# top-100-68-shield.net
KiCad netlist of a schematic drawn in EAGLE
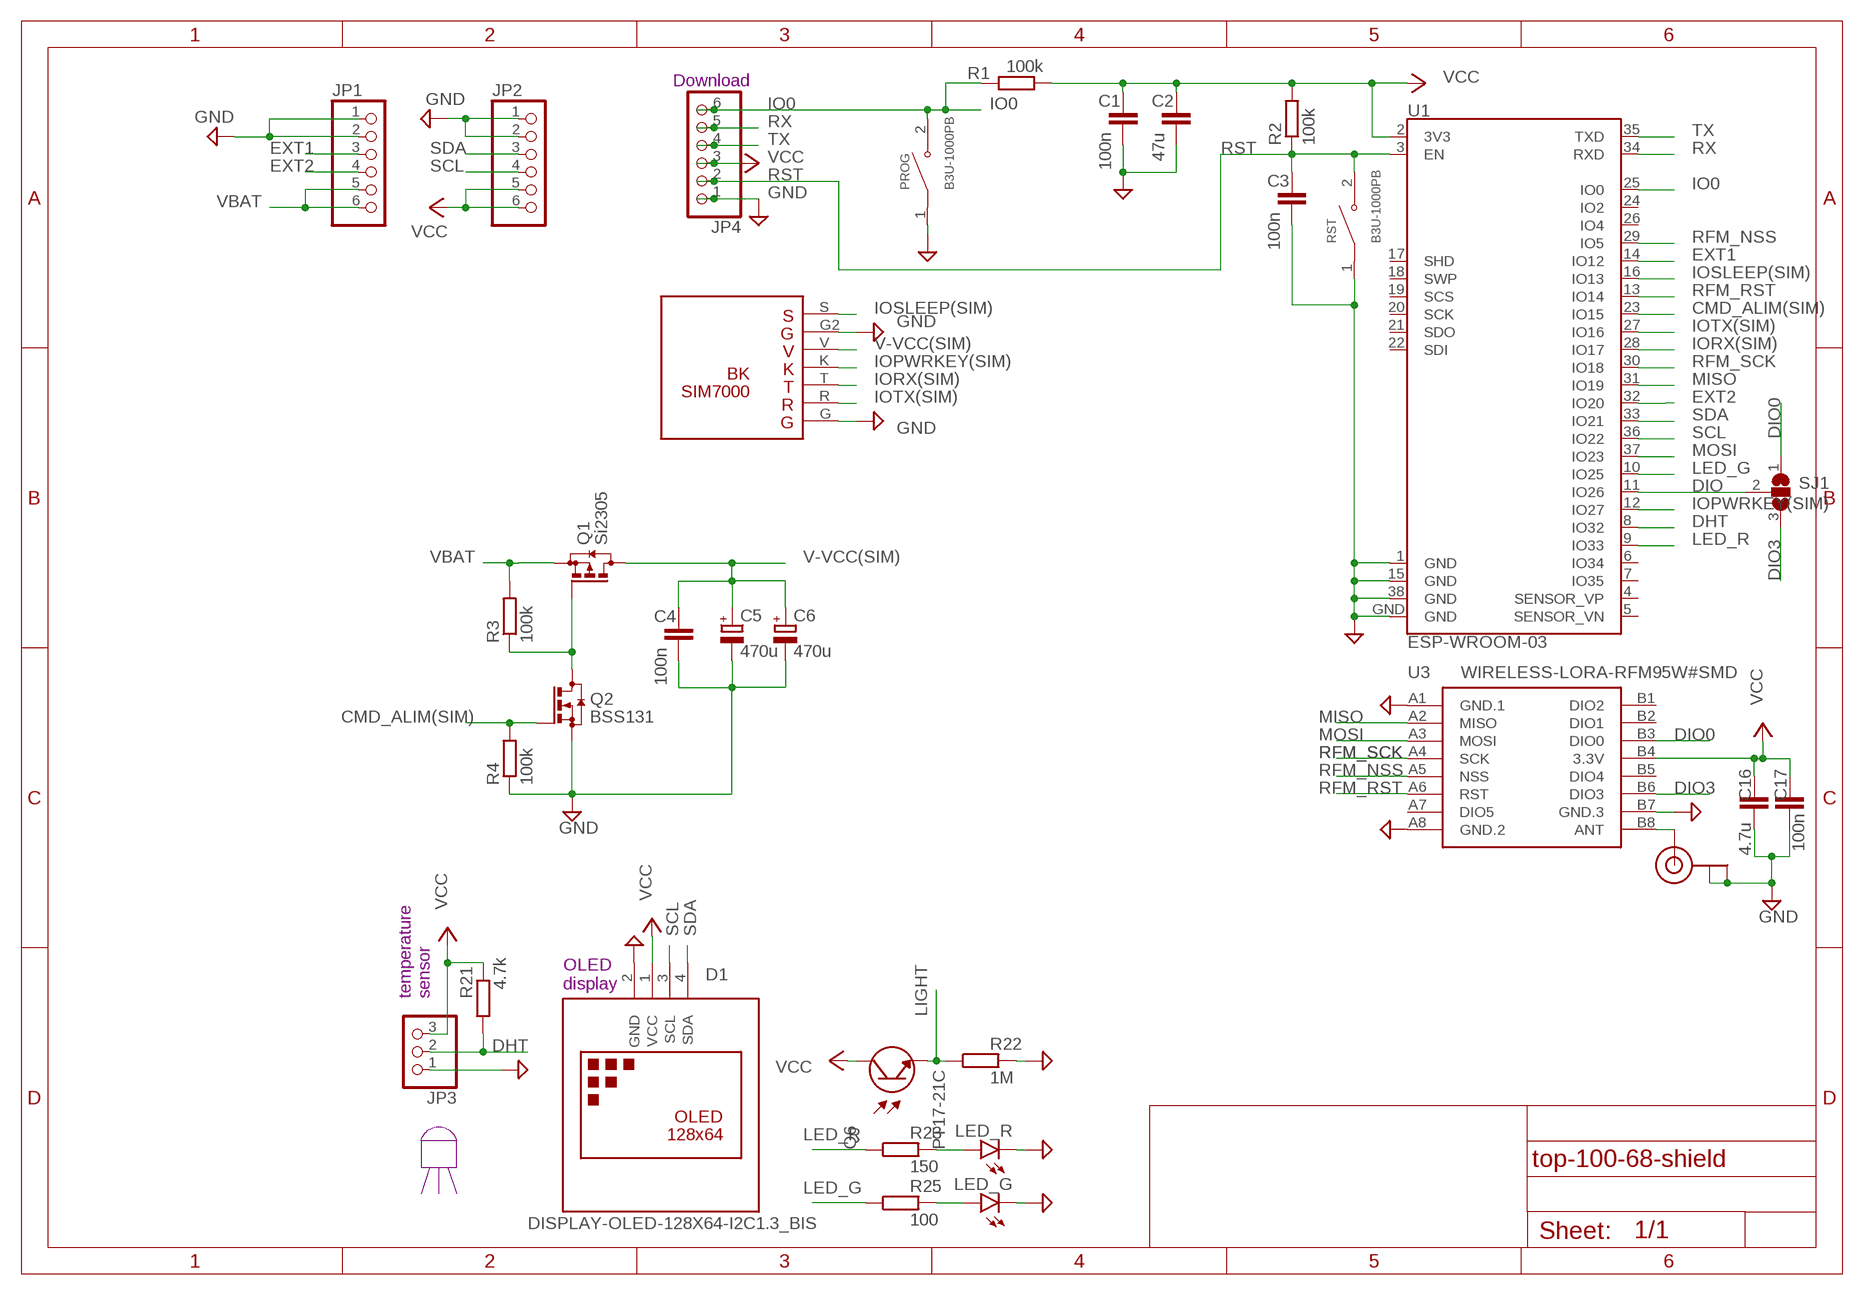
[diagram p0: schematic, sheet 1]

(export (version "E")
  (design (tool "Eeschema 10.0.6"))
  (components
    (comp (ref "C1")
      (value "100n")
      (footprint "eagle-import:C1206")
      (libsource (lib "eagle-import") (part "CC1206"))
    )
    (comp (ref "C2")
      (value "47u")
      (footprint "eagle-import:C0805")
      (libsource (lib "eagle-import") (part "C"))
    )
    (comp (ref "C3")
      (value "100n")
      (footprint "eagle-import:C1206")
      (libsource (lib "eagle-import") (part "CC1206"))
    )
    (comp (ref "C4")
      (value "100n")
      (footprint "eagle-import:C1206")
      (libsource (lib "eagle-import") (part "CC1206"))
    )
    (comp (ref "C5")
      (value "470u")
      (footprint "eagle-import:CT7343")
      (libsource (lib "eagle-import") (part "CPOL-EUCT7343"))
    )
    (comp (ref "C6")
      (value "470u")
      (footprint "eagle-import:CT7343")
      (libsource (lib "eagle-import") (part "CPOL-EUCT7343"))
    )
    (comp (ref "C16")
      (value "4.7u")
      (footprint "eagle-import:C1210")
      (libsource (lib "eagle-import") (part "CC1210"))
    )
    (comp (ref "C17")
      (value "100n")
      (footprint "eagle-import:C1206")
      (libsource (lib "eagle-import") (part "CC1206"))
    )
    (comp (ref "D1")
      (value "DISPLAY-OLED-128X64-I2C1.3_BIS")
      (footprint "eagle-import:DISPLAY-OLED-128X64-1.3-I2C_BIS")
      (libsource (lib "eagle-import") (part "DISPLAY-OLED-128X64-I2C1.3_BIS"))
    )
    (comp (ref "J1")
      (value "U.FL")
      (footprint "eagle-import:U.FL")
      (libsource (lib "eagle-import") (part "U.FL"))
    )
    (comp (ref "JP1")
      (value "PINHD-1X6S")
      (footprint "eagle-import:1X06S")
      (libsource (lib "eagle-import") (part "PINHD-1X6S"))
    )
    (comp (ref "JP2")
      (value "PINHD-1X6S")
      (footprint "eagle-import:1X06S")
      (libsource (lib "eagle-import") (part "PINHD-1X6S"))
    )
    (comp (ref "JP3")
      (value "PINHD-1X3")
      (footprint "eagle-import:1X03")
      (libsource (lib "eagle-import") (part "PINHD-1X3"))
    )
    (comp (ref "JP4")
      (value "PINHD-1X6S")
      (footprint "eagle-import:1X06S")
      (libsource (lib "eagle-import") (part "PINHD-1X6S"))
    )
    (comp (ref "LED_G")
      (value "LEDSMT1206")
      (footprint "eagle-import:1206")
      (libsource (lib "eagle-import") (part "LEDSMT1206"))
    )
    (comp (ref "LED_R")
      (value "LEDSMT1206")
      (footprint "eagle-import:1206")
      (libsource (lib "eagle-import") (part "LEDSMT1206"))
    )
    (comp (ref "PROG")
      (value "B3U-1000PB")
      (footprint "eagle-import:SW_B3U-1000PB")
      (libsource (lib "eagle-import") (part "B3U-1000PB"))
    )
    (comp (ref "Q1")
      (value "Si2305")
      (footprint "eagle-import:SOT23")
      (libsource (lib "eagle-import") (part "BSS84"))
    )
    (comp (ref "Q2")
      (value "BSS131")
      (footprint "eagle-import:SOT23")
      (libsource (lib "eagle-import") (part "BSS123"))
    )
    (comp (ref "Q6")
      (value "PT17-21C")
      (footprint "eagle-import:0805")
      (libsource (lib "eagle-import") (part "PT17-21C"))
    )
    (comp (ref "R1")
      (value "100k")
      (footprint "eagle-import:R1206")
      (libsource (lib "eagle-import") (part "RR1206"))
    )
    (comp (ref "R2")
      (value "100k")
      (footprint "eagle-import:R1206")
      (libsource (lib "eagle-import") (part "RR1206"))
    )
    (comp (ref "R3")
      (value "100k")
      (footprint "eagle-import:R1206")
      (libsource (lib "eagle-import") (part "RR1206"))
    )
    (comp (ref "R4")
      (value "100k")
      (footprint "eagle-import:R1206")
      (libsource (lib "eagle-import") (part "RR1206"))
    )
    (comp (ref "R21")
      (value "4.7k")
      (footprint "eagle-import:R1206")
      (libsource (lib "eagle-import") (part "RR1206"))
    )
    (comp (ref "R22")
      (value "1M")
      (footprint "eagle-import:R1206")
      (libsource (lib "eagle-import") (part "RR1206"))
    )
    (comp (ref "R23")
      (value "150")
      (footprint "eagle-import:R1206")
      (libsource (lib "eagle-import") (part "RR1206"))
    )
    (comp (ref "R25")
      (value "100")
      (footprint "eagle-import:R1206")
      (libsource (lib "eagle-import") (part "RR1206"))
    )
    (comp (ref "RST")
      (value "B3U-1000PB")
      (footprint "eagle-import:SW_B3U-1000PB")
      (libsource (lib "eagle-import") (part "B3U-1000PB"))
    )
    (comp (ref "SJ1")
      (value "SJ2W")
      (footprint "eagle-import:SJ_2")
      (libsource (lib "eagle-import") (part "SJ2W"))
    )
    (comp (ref "U1")
      (value "ESP-WROOM-03")
      (footprint "eagle-import:ESP-WROOM-03")
      (libsource (lib "eagle-import") (part "ESP-WROOM-03"))
    )
    (comp (ref "U2")
      (value "BK7000-V2")
      (footprint "eagle-import:SIM7000-BK")
      (libsource (lib "eagle-import") (part "BK7000-V2"))
    )
    (comp (ref "U3")
      (value "WIRELESS-LORA-RFM95W#SMD")
      (footprint "eagle-import:WIRELESS-LORA-RFM95W#SMD")
      (libsource (lib "eagle-import") (part "WIRELESS-LORA-RFM95W#SMD"))
    )
  )
  (nets
    (net (code "1") (name "/CMD_ALIM(SIM)") (class "Default")
      (node (ref "Q2") (pin "1") (pinfunction "G_1") (pintype "passive"))
      (node (ref "R4") (pin "2") (pinfunction "2_2") (pintype "passive"))
      (node (ref "U1") (pin "23") (pinfunction "IO15_23") (pintype "bidirectional"))
    )
    (net (code "2") (name "/DHT") (class "Default")
      (node (ref "JP3") (pin "2") (pinfunction "2_2") (pintype "passive"))
      (node (ref "R21") (pin "1") (pinfunction "1_1") (pintype "passive"))
      (node (ref "U1") (pin "8") (pinfunction "IO32_8") (pintype "bidirectional"))
    )
    (net (code "3") (name "/DIO") (class "Default")
      (node (ref "SJ1") (pin "2") (pinfunction "2_2") (pintype "passive"))
      (node (ref "U1") (pin "11") (pinfunction "IO26_11") (pintype "bidirectional"))
    )
    (net (code "4") (name "/DIO0") (class "Default")
      (node (ref "SJ1") (pin "1") (pinfunction "1_1") (pintype "passive"))
      (node (ref "U3") (pin "B3") (pinfunction "DIO0_B3") (pintype "bidirectional"))
    )
    (net (code "5") (name "/DIO3") (class "Default")
      (node (ref "SJ1") (pin "3") (pinfunction "3_3") (pintype "passive"))
      (node (ref "U3") (pin "B6") (pinfunction "DIO3_B6") (pintype "bidirectional"))
    )
    (net (code "6") (name "/EXT1") (class "Default")
      (node (ref "JP1") (pin "3") (pinfunction "3_3") (pintype "passive"))
      (node (ref "U1") (pin "14") (pinfunction "IO12_14") (pintype "bidirectional"))
    )
    (net (code "7") (name "/EXT2") (class "Default")
      (node (ref "JP1") (pin "4") (pinfunction "4_4") (pintype "passive"))
      (node (ref "U1") (pin "32") (pinfunction "IO20_32") (pintype "bidirectional"))
    )
    (net (code "8") (name "/IO0") (class "Default")
      (node (ref "JP4") (pin "6") (pinfunction "6_6") (pintype "passive"))
      (node (ref "PROG") (pin "2") (pinfunction "2_2") (pintype "passive"))
      (node (ref "R1") (pin "2") (pinfunction "2_2") (pintype "passive"))
      (node (ref "U1") (pin "25") (pinfunction "IO0_25") (pintype "bidirectional"))
    )
    (net (code "9") (name "/IOPWRKEY(SIM)") (class "Default")
      (node (ref "U1") (pin "12") (pinfunction "IO27_12") (pintype "bidirectional"))
      (node (ref "U2") (pin "K") (pinfunction "K_K") (pintype "output"))
    )
    (net (code "10") (name "/IORX(SIM)") (class "Default")
      (node (ref "U1") (pin "28") (pinfunction "IO17_28") (pintype "bidirectional"))
      (node (ref "U2") (pin "T") (pinfunction "T_T") (pintype "output"))
    )
    (net (code "11") (name "/IOSLEEP(SIM)") (class "Default")
      (node (ref "U1") (pin "16") (pinfunction "IO13_16") (pintype "bidirectional"))
      (node (ref "U2") (pin "S") (pinfunction "S_S") (pintype "input"))
    )
    (net (code "12") (name "/IOTX(SIM)") (class "Default")
      (node (ref "U1") (pin "27") (pinfunction "IO16_27") (pintype "bidirectional"))
      (node (ref "U2") (pin "R") (pinfunction "R_R") (pintype "input"))
    )
    (net (code "13") (name "/LED_G") (class "Default")
      (node (ref "R25") (pin "1") (pinfunction "1_1") (pintype "passive"))
      (node (ref "U1") (pin "10") (pinfunction "IO25_10") (pintype "bidirectional"))
    )
    (net (code "14") (name "/LED_R") (class "Default")
      (node (ref "R23") (pin "1") (pinfunction "1_1") (pintype "passive"))
      (node (ref "U1") (pin "9") (pinfunction "IO33_9") (pintype "bidirectional"))
    )
    (net (code "15") (name "/LIGHT") (class "Default")
      (node (ref "Q6") (pin "1") (pinfunction "E_1") (pintype "passive"))
      (node (ref "R22") (pin "1") (pinfunction "1_1") (pintype "passive"))
    )
    (net (code "16") (name "/MISO") (class "Default")
      (node (ref "U1") (pin "31") (pinfunction "IO19_31") (pintype "bidirectional"))
      (node (ref "U3") (pin "A2") (pinfunction "MISO_A2") (pintype "bidirectional"))
    )
    (net (code "17") (name "/MOSI") (class "Default")
      (node (ref "U1") (pin "37") (pinfunction "IO23_37") (pintype "bidirectional"))
      (node (ref "U3") (pin "A3") (pinfunction "MOSI_A3") (pintype "bidirectional"))
    )
    (net (code "18") (name "/RFM_NSS") (class "Default")
      (node (ref "U1") (pin "29") (pinfunction "IO5_29") (pintype "bidirectional"))
      (node (ref "U3") (pin "A5") (pinfunction "NSS_A5") (pintype "bidirectional"))
    )
    (net (code "19") (name "/RFM_RST") (class "Default")
      (node (ref "U1") (pin "13") (pinfunction "IO14_13") (pintype "bidirectional"))
      (node (ref "U3") (pin "A6") (pinfunction "RST_A6") (pintype "bidirectional"))
    )
    (net (code "20") (name "/RFM_SCK") (class "Default")
      (node (ref "U1") (pin "30") (pinfunction "IO18_30") (pintype "bidirectional"))
      (node (ref "U3") (pin "A4") (pinfunction "SCK_A4") (pintype "bidirectional"))
    )
    (net (code "21") (name "/RST") (class "Default")
      (node (ref "C3") (pin "1") (pinfunction "1_1") (pintype "passive"))
      (node (ref "JP4") (pin "2") (pinfunction "2_2") (pintype "passive"))
      (node (ref "R2") (pin "1") (pinfunction "1_1") (pintype "passive"))
      (node (ref "RST") (pin "2") (pinfunction "2_2") (pintype "passive"))
      (node (ref "U1") (pin "3") (pinfunction "EN_3") (pintype "bidirectional"))
    )
    (net (code "22") (name "/RX") (class "Default")
      (node (ref "JP4") (pin "5") (pinfunction "5_5") (pintype "passive"))
      (node (ref "U1") (pin "34") (pinfunction "RXD_34") (pintype "bidirectional"))
    )
    (net (code "23") (name "/SCL") (class "Default")
      (node (ref "D1") (pin "3") (pinfunction "SCL_3") (pintype "bidirectional"))
      (node (ref "JP2") (pin "4") (pinfunction "4_4") (pintype "passive"))
      (node (ref "U1") (pin "36") (pinfunction "IO22_36") (pintype "bidirectional"))
    )
    (net (code "24") (name "/SDA") (class "Default")
      (node (ref "D1") (pin "4") (pinfunction "SDA_4") (pintype "bidirectional"))
      (node (ref "JP2") (pin "3") (pinfunction "3_3") (pintype "passive"))
      (node (ref "U1") (pin "33") (pinfunction "IO21_33") (pintype "bidirectional"))
    )
    (net (code "25") (name "/TX") (class "Default")
      (node (ref "JP4") (pin "4") (pinfunction "4_4") (pintype "passive"))
      (node (ref "U1") (pin "35") (pinfunction "TXD_35") (pintype "bidirectional"))
    )
    (net (code "26") (name "/V-VCC(SIM)") (class "Default")
      (node (ref "C4") (pin "1") (pinfunction "1_1") (pintype "passive"))
      (node (ref "C5") (pin "+") (pinfunction "+_+") (pintype "passive"))
      (node (ref "C6") (pin "+") (pinfunction "+_+") (pintype "passive"))
      (node (ref "Q1") (pin "3") (pinfunction "D_3") (pintype "passive"))
      (node (ref "U2") (pin "V") (pinfunction "V_V") (pintype "power_in"))
    )
    (net (code "27") (name "/VBAT") (class "Default")
      (node (ref "JP1") (pin "5") (pinfunction "5_5") (pintype "passive"))
      (node (ref "JP1") (pin "6") (pinfunction "6_6") (pintype "passive"))
      (node (ref "Q1") (pin "2") (pinfunction "S_2") (pintype "passive"))
      (node (ref "R3") (pin "2") (pinfunction "2_2") (pintype "passive"))
    )
    (net (code "28") (name "GND") (class "Default")
      (node (ref "C1") (pin "2") (pinfunction "2_2") (pintype "passive"))
      (node (ref "C16") (pin "2") (pinfunction "2_2") (pintype "passive"))
      (node (ref "C17") (pin "2") (pinfunction "2_2") (pintype "passive"))
      (node (ref "C2") (pin "2") (pinfunction "2_2") (pintype "passive"))
      (node (ref "C3") (pin "2") (pinfunction "2_2") (pintype "passive"))
      (node (ref "C4") (pin "2") (pinfunction "2_2") (pintype "passive"))
      (node (ref "C5") (pin "-") (pinfunction "-_-") (pintype "passive"))
      (node (ref "C6") (pin "-") (pinfunction "-_-") (pintype "passive"))
      (node (ref "D1") (pin "2") (pinfunction "GND_2") (pintype "power_in"))
      (node (ref "J1") (pin "1") (pinfunction "GND_1") (pintype "passive"))
      (node (ref "J1") (pin "2") (pinfunction "GND_2") (pintype "passive"))
      (node (ref "JP1") (pin "1") (pinfunction "1_1") (pintype "passive"))
      (node (ref "JP1") (pin "2") (pinfunction "2_2") (pintype "passive"))
      (node (ref "JP2") (pin "1") (pinfunction "1_1") (pintype "passive"))
      (node (ref "JP2") (pin "2") (pinfunction "2_2") (pintype "passive"))
      (node (ref "JP3") (pin "1") (pinfunction "1_1") (pintype "passive"))
      (node (ref "JP4") (pin "1") (pinfunction "1_1") (pintype "passive"))
      (node (ref "LED_G") (pin "C") (pinfunction "C_C") (pintype "passive"))
      (node (ref "LED_R") (pin "C") (pinfunction "C_C") (pintype "passive"))
      (node (ref "PROG") (pin "1") (pinfunction "1_1") (pintype "passive"))
      (node (ref "Q2") (pin "2") (pinfunction "S_2") (pintype "passive"))
      (node (ref "R22") (pin "2") (pinfunction "2_2") (pintype "passive"))
      (node (ref "R4") (pin "1") (pinfunction "1_1") (pintype "passive"))
      (node (ref "RST") (pin "1") (pinfunction "1_1") (pintype "passive"))
      (node (ref "U1") (pin "1") (pinfunction "GND_1") (pintype "bidirectional"))
      (node (ref "U1") (pin "15") (pinfunction "GND_15") (pintype "bidirectional"))
      (node (ref "U1") (pin "38") (pinfunction "GND_38") (pintype "bidirectional"))
      (node (ref "U1") (pin "GND") (pinfunction "GND_GND") (pintype "bidirectional"))
      (node (ref "U2") (pin "G") (pinfunction "G_G") (pintype "power_in"))
      (node (ref "U2") (pin "G2") (pinfunction "G2_G2") (pintype "power_in"))
      (node (ref "U3") (pin "A1") (pinfunction "GND.1_A1") (pintype "power_in"))
      (node (ref "U3") (pin "A8") (pinfunction "GND.2_A8") (pintype "power_in"))
      (node (ref "U3") (pin "B7") (pinfunction "GND.3_B7") (pintype "power_in"))
    )
    (net (code "29") (name "Net-(J1-SIGNAL)") (class "Default")
      (node (ref "J1") (pin "3") (pinfunction "SIGNAL_3") (pintype "passive"))
      (node (ref "U3") (pin "B8") (pinfunction "ANT_B8") (pintype "passive"))
    )
    (net (code "30") (name "Net-(LED_G-PadA)") (class "Default")
      (node (ref "LED_G") (pin "A") (pinfunction "A_A") (pintype "passive"))
      (node (ref "R25") (pin "2") (pinfunction "2_2") (pintype "passive"))
    )
    (net (code "31") (name "Net-(LED_R-PadA)") (class "Default")
      (node (ref "LED_R") (pin "A") (pinfunction "A_A") (pintype "passive"))
      (node (ref "R23") (pin "2") (pinfunction "2_2") (pintype "passive"))
    )
    (net (code "32") (name "Net-(Q1-G)") (class "Default")
      (node (ref "Q1") (pin "1") (pinfunction "G_1") (pintype "passive"))
      (node (ref "Q2") (pin "3") (pinfunction "D_3") (pintype "passive"))
      (node (ref "R3") (pin "1") (pinfunction "1_1") (pintype "passive"))
    )
    (net (code "33") (name "VCC") (class "Default")
      (node (ref "C1") (pin "1") (pinfunction "1_1") (pintype "passive"))
      (node (ref "C16") (pin "1") (pinfunction "1_1") (pintype "passive"))
      (node (ref "C17") (pin "1") (pinfunction "1_1") (pintype "passive"))
      (node (ref "C2") (pin "1") (pinfunction "1_1") (pintype "passive"))
      (node (ref "D1") (pin "1") (pinfunction "VCC_1") (pintype "power_in"))
      (node (ref "JP2") (pin "5") (pinfunction "5_5") (pintype "passive"))
      (node (ref "JP2") (pin "6") (pinfunction "6_6") (pintype "passive"))
      (node (ref "JP3") (pin "3") (pinfunction "3_3") (pintype "passive"))
      (node (ref "JP4") (pin "3") (pinfunction "3_3") (pintype "passive"))
      (node (ref "Q6") (pin "2") (pinfunction "C_2") (pintype "passive"))
      (node (ref "R1") (pin "1") (pinfunction "1_1") (pintype "passive"))
      (node (ref "R2") (pin "2") (pinfunction "2_2") (pintype "passive"))
      (node (ref "R21") (pin "2") (pinfunction "2_2") (pintype "passive"))
      (node (ref "U1") (pin "2") (pinfunction "3V3_2") (pintype "bidirectional"))
      (node (ref "U3") (pin "B4") (pinfunction "3.3V_B4") (pintype "power_in"))
    )
    (net (code "34") (name "unconnected-(U1-IO2-Pad24)") (class "Default")
      (node (ref "U1") (pin "24") (pinfunction "IO2_24") (pintype "bidirectional"))
    )
    (net (code "35") (name "unconnected-(U1-IO4-Pad26)") (class "Default")
      (node (ref "U1") (pin "26") (pinfunction "IO4_26") (pintype "bidirectional"))
    )
    (net (code "36") (name "unconnected-(U1-IO34-Pad6)") (class "Default")
      (node (ref "U1") (pin "6") (pinfunction "IO34_6") (pintype "bidirectional"))
    )
    (net (code "37") (name "unconnected-(U1-IO35-Pad7)") (class "Default")
      (node (ref "U1") (pin "7") (pinfunction "IO35_7") (pintype "bidirectional"))
    )
    (net (code "38") (name "unconnected-(U1-SCK-Pad20)") (class "Default")
      (node (ref "U1") (pin "20") (pinfunction "SCK_20") (pintype "bidirectional"))
    )
    (net (code "39") (name "unconnected-(U1-SCS-Pad19)") (class "Default")
      (node (ref "U1") (pin "19") (pinfunction "SCS_19") (pintype "bidirectional"))
    )
    (net (code "40") (name "unconnected-(U1-SDI-Pad22)") (class "Default")
      (node (ref "U1") (pin "22") (pinfunction "SDI_22") (pintype "bidirectional"))
    )
    (net (code "41") (name "unconnected-(U1-SDO-Pad21)") (class "Default")
      (node (ref "U1") (pin "21") (pinfunction "SDO_21") (pintype "bidirectional"))
    )
    (net (code "42") (name "unconnected-(U1-SENSOR_VN-Pad5)") (class "Default")
      (node (ref "U1") (pin "5") (pinfunction "SENSOR_VN_5") (pintype "bidirectional"))
    )
    (net (code "43") (name "unconnected-(U1-SENSOR_VP-Pad4)") (class "Default")
      (node (ref "U1") (pin "4") (pinfunction "SENSOR_VP_4") (pintype "bidirectional"))
    )
    (net (code "44") (name "unconnected-(U1-SHD-Pad17)") (class "Default")
      (node (ref "U1") (pin "17") (pinfunction "SHD_17") (pintype "bidirectional"))
    )
    (net (code "45") (name "unconnected-(U1-SWP-Pad18)") (class "Default")
      (node (ref "U1") (pin "18") (pinfunction "SWP_18") (pintype "bidirectional"))
    )
    (net (code "46") (name "unconnected-(U3-DIO1-PadB2)") (class "Default")
      (node (ref "U3") (pin "B2") (pinfunction "DIO1_B2") (pintype "bidirectional"))
    )
    (net (code "47") (name "unconnected-(U3-DIO2-PadB1)") (class "Default")
      (node (ref "U3") (pin "B1") (pinfunction "DIO2_B1") (pintype "bidirectional"))
    )
    (net (code "48") (name "unconnected-(U3-DIO4-PadB5)") (class "Default")
      (node (ref "U3") (pin "B5") (pinfunction "DIO4_B5") (pintype "bidirectional"))
    )
    (net (code "49") (name "unconnected-(U3-DIO5-PadA7)") (class "Default")
      (node (ref "U3") (pin "A7") (pinfunction "DIO5_A7") (pintype "bidirectional"))
    )
  )
)
